# drive.net
KiCad netlist of a schematic drawn in Altium Designer
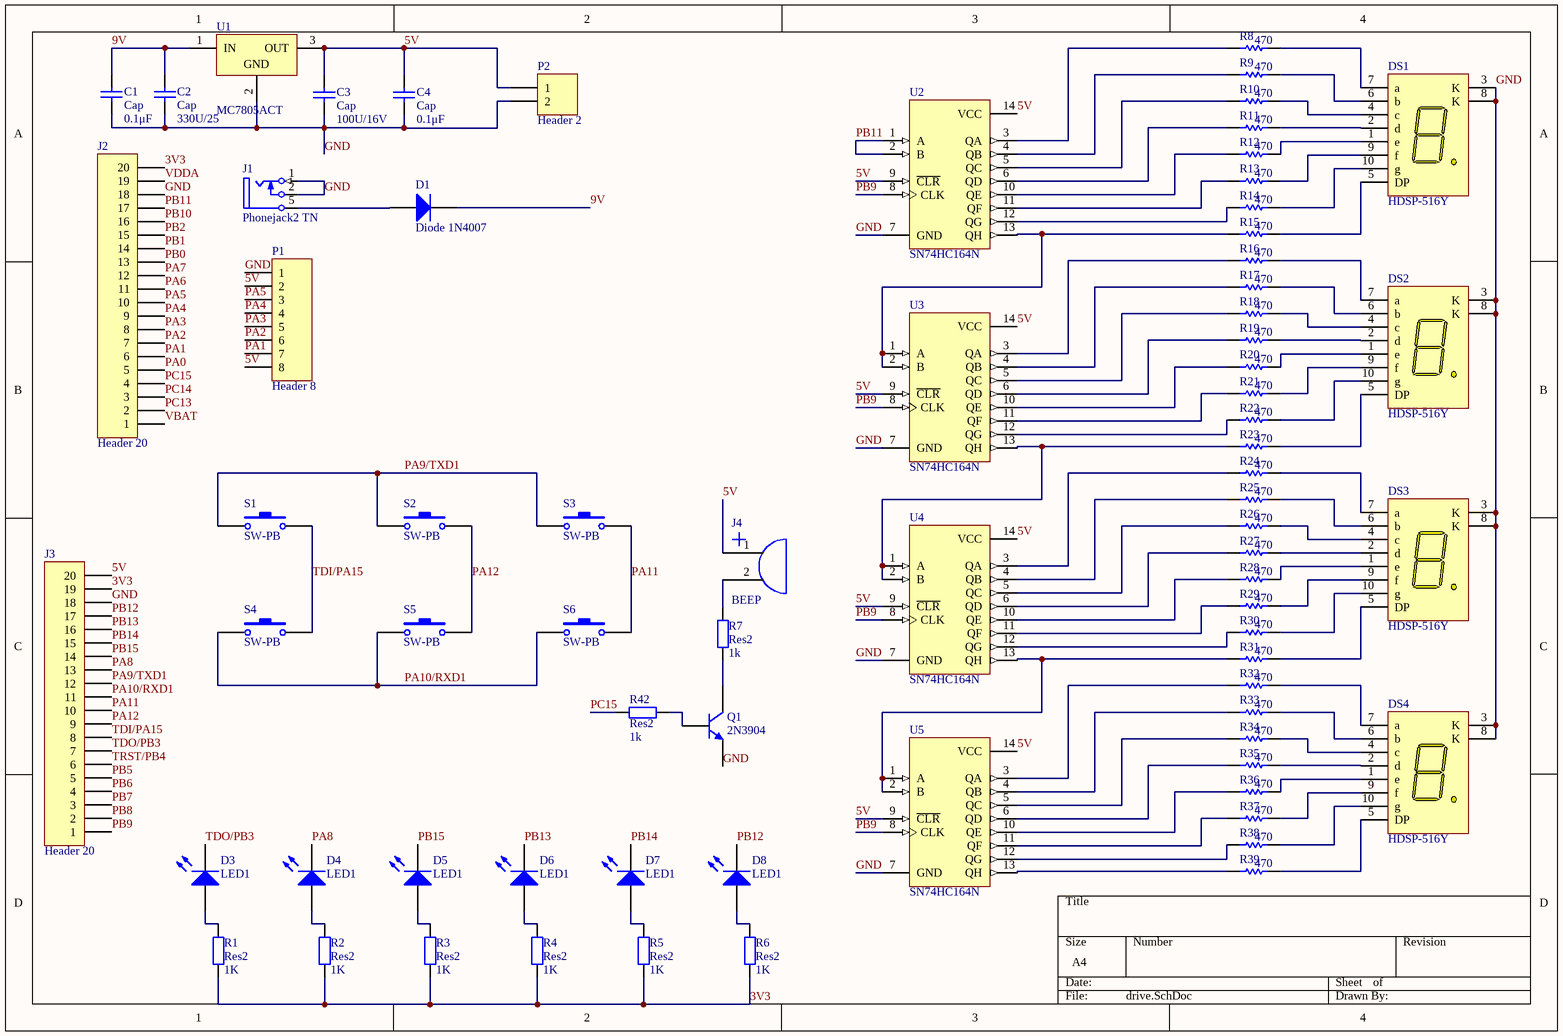
[diagram p0: drive.SchDoc]

(export (version "E")
  (design (tool "Eeschema 10.0.6"))
  (components
    (comp (ref "C1")
      (value "Cap")
      (footprint "RAD-0.3")
      (description "Capacitor")
      (fields (field (name "ALTIUM_VALUE") "0.1μF") (field (name "PUBLISHER") "Altium Limited"))
      (libsource (lib "Miscellaneous Devices") (part "Cap"))
    )
    (comp (ref "C2")
      (value "Cap")
      (footprint "RAD-0.3")
      (description "Capacitor")
      (fields (field (name "ALTIUM_VALUE") "330U/25") (field (name "PUBLISHER") "Altium Limited"))
      (libsource (lib "Miscellaneous Devices") (part "Cap"))
    )
    (comp (ref "C3")
      (value "Cap")
      (footprint "RAD-0.3")
      (description "Capacitor")
      (fields (field (name "ALTIUM_VALUE") "100U/16V") (field (name "PUBLISHER") "Altium Limited"))
      (libsource (lib "Miscellaneous Devices") (part "Cap"))
    )
    (comp (ref "C4")
      (value "Cap")
      (footprint "RAD-0.3")
      (description "Capacitor")
      (fields (field (name "ALTIUM_VALUE") "0.1μF") (field (name "PUBLISHER") "Altium Limited"))
      (libsource (lib "Miscellaneous Devices") (part "Cap"))
    )
    (comp (ref "D1")
      (value "Diode 1N4007")
      (footprint "DO-41")
      (description "1 Amp General Purpose Rectifier")
      (fields (field (name "PUBLISHER") "Altium Limited"))
      (libsource (lib "Miscellaneous Devices") (part "Diode 1N4007"))
    )
    (comp (ref "D3")
      (value "LED1")
      (footprint "LED-1")
      (description "Typical RED GaAs LED")
      (fields (field (name "PUBLISHER") "Altium Limited"))
      (libsource (lib "Miscellaneous Devices") (part "LED1"))
    )
    (comp (ref "D4")
      (value "LED1")
      (footprint "LED-1")
      (description "Typical RED GaAs LED")
      (fields (field (name "PUBLISHER") "Altium Limited"))
      (libsource (lib "Miscellaneous Devices") (part "LED1"))
    )
    (comp (ref "D5")
      (value "LED1")
      (footprint "LED-1")
      (description "Typical RED GaAs LED")
      (fields (field (name "PUBLISHER") "Altium Limited"))
      (libsource (lib "Miscellaneous Devices") (part "LED1"))
    )
    (comp (ref "D6")
      (value "LED1")
      (footprint "LED-1")
      (description "Typical RED GaAs LED")
      (fields (field (name "PUBLISHER") "Altium Limited"))
      (libsource (lib "Miscellaneous Devices") (part "LED1"))
    )
    (comp (ref "D7")
      (value "LED1")
      (footprint "LED-1")
      (description "Typical RED GaAs LED")
      (fields (field (name "PUBLISHER") "Altium Limited"))
      (libsource (lib "Miscellaneous Devices") (part "LED1"))
    )
    (comp (ref "D8")
      (value "LED1")
      (footprint "LED-1")
      (description "Typical RED GaAs LED")
      (fields (field (name "PUBLISHER") "Altium Limited"))
      (libsource (lib "Miscellaneous Devices") (part "LED1"))
    )
    (comp (ref "DS1")
      (value "HDSP-516Y")
      (footprint "Case-5")
      (description "13 mm Slim Font, Standard Current, Yellow 7-Segment Display: CC, RH DP")
      (fields (field (name "PUBLISHER") "Altium Limited"))
      (libsource (lib "Agilent LED Display 7-Segment, 1-Digit") (part "HDSP-516Y"))
    )
    (comp (ref "DS2")
      (value "HDSP-516Y")
      (footprint "Case-5")
      (description "13 mm Slim Font, Standard Current, Yellow 7-Segment Display: CC, RH DP")
      (fields (field (name "PUBLISHER") "Altium Limited"))
      (libsource (lib "Agilent LED Display 7-Segment, 1-Digit") (part "HDSP-516Y"))
    )
    (comp (ref "DS3")
      (value "HDSP-516Y")
      (footprint "Case-5")
      (description "13 mm Slim Font, Standard Current, Yellow 7-Segment Display: CC, RH DP")
      (fields (field (name "PUBLISHER") "Altium Limited"))
      (libsource (lib "Agilent LED Display 7-Segment, 1-Digit") (part "HDSP-516Y"))
    )
    (comp (ref "DS4")
      (value "HDSP-516Y")
      (footprint "Case-5")
      (description "13 mm Slim Font, Standard Current, Yellow 7-Segment Display: CC, RH DP")
      (fields (field (name "PUBLISHER") "Altium Limited"))
      (libsource (lib "Agilent LED Display 7-Segment, 1-Digit") (part "HDSP-516Y"))
    )
    (comp (ref "J1")
      (value "Phonejack2 TN")
      (footprint "DC-005")
      (description "Jack Socket, 1/4\" [6.5mm], Thru-Hole, Vertical, 2-Conductor with Tip closed")
      (fields (field (name "PUBLISHER") "Altium Limited"))
      (libsource (lib "Miscellaneous Connectors") (part "Phonejack2 TN"))
    )
    (comp (ref "J2")
      (value "Header 20")
      (footprint "HDR1X20")
      (description "Header, 20-Pin")
      (fields (field (name "PUBLISHER") "Altium Limited"))
      (libsource (lib "Miscellaneous Connectors") (part "Header 20"))
    )
    (comp (ref "J3")
      (value "Header 20")
      (footprint "HDR1X20")
      (description "Header, 20-Pin")
      (fields (field (name "PUBLISHER") "Altium Limited"))
      (libsource (lib "Miscellaneous Connectors") (part "Header 20"))
    )
    (comp (ref "J4")
      (value "BEEP")
      (footprint "Beep")
      (description "蜂鸣器")
      (libsource (lib "TSLone") (part "BEEP"))
    )
    (comp (ref "P1")
      (value "Header 8")
      (footprint "HDR1X8")
      (description "Header, 8-Pin")
      (fields (field (name "PUBLISHER") "Altium Limited"))
      (libsource (lib "Miscellaneous Connectors") (part "Header 8"))
    )
    (comp (ref "P2")
      (value "Header 2")
      (footprint "HDR1X2")
      (description "Header, 2-Pin")
      (fields (field (name "PUBLISHER") "Altium Limited"))
      (libsource (lib "Miscellaneous Connectors") (part "Header 2"))
    )
    (comp (ref "Q1")
      (value "2N3904")
      (footprint "TO-92A")
      (description "NPN General Purpose Amplifier")
      (fields (field (name "PUBLISHER") "Altium Limited"))
      (libsource (lib "Miscellaneous Devices") (part "2N3904"))
    )
    (comp (ref "R1")
      (value "Res2")
      (footprint "AXIAL-0.4")
      (description "Resistor")
      (fields (field (name "ALTIUM_VALUE") "1K") (field (name "PUBLISHER") "Altium Limited"))
      (libsource (lib "Miscellaneous Devices") (part "Res2"))
    )
    (comp (ref "R2")
      (value "Res2")
      (footprint "AXIAL-0.4")
      (description "Resistor")
      (fields (field (name "ALTIUM_VALUE") "1K") (field (name "PUBLISHER") "Altium Limited"))
      (libsource (lib "Miscellaneous Devices") (part "Res2"))
    )
    (comp (ref "R3")
      (value "Res2")
      (footprint "AXIAL-0.4")
      (description "Resistor")
      (fields (field (name "ALTIUM_VALUE") "1K") (field (name "PUBLISHER") "Altium Limited"))
      (libsource (lib "Miscellaneous Devices") (part "Res2"))
    )
    (comp (ref "R4")
      (value "Res2")
      (footprint "AXIAL-0.4")
      (description "Resistor")
      (fields (field (name "ALTIUM_VALUE") "1K") (field (name "PUBLISHER") "Altium Limited"))
      (libsource (lib "Miscellaneous Devices") (part "Res2"))
    )
    (comp (ref "R5")
      (value "Res2")
      (footprint "AXIAL-0.4")
      (description "Resistor")
      (fields (field (name "ALTIUM_VALUE") "1K") (field (name "PUBLISHER") "Altium Limited"))
      (libsource (lib "Miscellaneous Devices") (part "Res2"))
    )
    (comp (ref "R6")
      (value "Res2")
      (footprint "AXIAL-0.4")
      (description "Resistor")
      (fields (field (name "ALTIUM_VALUE") "1K") (field (name "PUBLISHER") "Altium Limited"))
      (libsource (lib "Miscellaneous Devices") (part "Res2"))
    )
    (comp (ref "R7")
      (value "Res2")
      (footprint "AXIAL-0.4")
      (description "Resistor")
      (fields (field (name "ALTIUM_VALUE") "1k") (field (name "PUBLISHER") "Altium Limited"))
      (libsource (lib "Miscellaneous Devices") (part "Res2"))
    )
    (comp (ref "R8")
      (value "470")
      (footprint "AXIAL-0.3")
      (description "Resistor")
      (fields (field (name "Comment") "Res1") (field (name "PUBLISHER") "Altium Limited"))
      (libsource (lib "Miscellaneous Devices") (part "Res1"))
    )
    (comp (ref "R9")
      (value "470")
      (footprint "AXIAL-0.3")
      (description "Resistor")
      (fields (field (name "Comment") "Res1") (field (name "PUBLISHER") "Altium Limited"))
      (libsource (lib "Miscellaneous Devices") (part "Res1"))
    )
    (comp (ref "R10")
      (value "470")
      (footprint "AXIAL-0.3")
      (description "Resistor")
      (fields (field (name "Comment") "Res1") (field (name "PUBLISHER") "Altium Limited"))
      (libsource (lib "Miscellaneous Devices") (part "Res1"))
    )
    (comp (ref "R11")
      (value "470")
      (footprint "AXIAL-0.3")
      (description "Resistor")
      (fields (field (name "Comment") "Res1") (field (name "PUBLISHER") "Altium Limited"))
      (libsource (lib "Miscellaneous Devices") (part "Res1"))
    )
    (comp (ref "R12")
      (value "470")
      (footprint "AXIAL-0.3")
      (description "Resistor")
      (fields (field (name "Comment") "Res1") (field (name "PUBLISHER") "Altium Limited"))
      (libsource (lib "Miscellaneous Devices") (part "Res1"))
    )
    (comp (ref "R13")
      (value "470")
      (footprint "AXIAL-0.3")
      (description "Resistor")
      (fields (field (name "Comment") "Res1") (field (name "PUBLISHER") "Altium Limited"))
      (libsource (lib "Miscellaneous Devices") (part "Res1"))
    )
    (comp (ref "R14")
      (value "470")
      (footprint "AXIAL-0.3")
      (description "Resistor")
      (fields (field (name "Comment") "Res1") (field (name "PUBLISHER") "Altium Limited"))
      (libsource (lib "Miscellaneous Devices") (part "Res1"))
    )
    (comp (ref "R15")
      (value "470")
      (footprint "AXIAL-0.3")
      (description "Resistor")
      (fields (field (name "Comment") "Res1") (field (name "PUBLISHER") "Altium Limited"))
      (libsource (lib "Miscellaneous Devices") (part "Res1"))
    )
    (comp (ref "R16")
      (value "470")
      (footprint "AXIAL-0.3")
      (description "Resistor")
      (fields (field (name "Comment") "Res1") (field (name "PUBLISHER") "Altium Limited"))
      (libsource (lib "Miscellaneous Devices") (part "Res1"))
    )
    (comp (ref "R17")
      (value "470")
      (footprint "AXIAL-0.3")
      (description "Resistor")
      (fields (field (name "Comment") "Res1") (field (name "PUBLISHER") "Altium Limited"))
      (libsource (lib "Miscellaneous Devices") (part "Res1"))
    )
    (comp (ref "R18")
      (value "470")
      (footprint "AXIAL-0.3")
      (description "Resistor")
      (fields (field (name "Comment") "Res1") (field (name "PUBLISHER") "Altium Limited"))
      (libsource (lib "Miscellaneous Devices") (part "Res1"))
    )
    (comp (ref "R19")
      (value "470")
      (footprint "AXIAL-0.3")
      (description "Resistor")
      (fields (field (name "Comment") "Res1") (field (name "PUBLISHER") "Altium Limited"))
      (libsource (lib "Miscellaneous Devices") (part "Res1"))
    )
    (comp (ref "R20")
      (value "470")
      (footprint "AXIAL-0.3")
      (description "Resistor")
      (fields (field (name "Comment") "Res1") (field (name "PUBLISHER") "Altium Limited"))
      (libsource (lib "Miscellaneous Devices") (part "Res1"))
    )
    (comp (ref "R21")
      (value "470")
      (footprint "AXIAL-0.3")
      (description "Resistor")
      (fields (field (name "Comment") "Res1") (field (name "PUBLISHER") "Altium Limited"))
      (libsource (lib "Miscellaneous Devices") (part "Res1"))
    )
    (comp (ref "R22")
      (value "470")
      (footprint "AXIAL-0.3")
      (description "Resistor")
      (fields (field (name "Comment") "Res1") (field (name "PUBLISHER") "Altium Limited"))
      (libsource (lib "Miscellaneous Devices") (part "Res1"))
    )
    (comp (ref "R23")
      (value "470")
      (footprint "AXIAL-0.3")
      (description "Resistor")
      (fields (field (name "Comment") "Res1") (field (name "PUBLISHER") "Altium Limited"))
      (libsource (lib "Miscellaneous Devices") (part "Res1"))
    )
    (comp (ref "R24")
      (value "470")
      (footprint "AXIAL-0.3")
      (description "Resistor")
      (fields (field (name "Comment") "Res1") (field (name "PUBLISHER") "Altium Limited"))
      (libsource (lib "Miscellaneous Devices") (part "Res1"))
    )
    (comp (ref "R25")
      (value "470")
      (footprint "AXIAL-0.3")
      (description "Resistor")
      (fields (field (name "Comment") "Res1") (field (name "PUBLISHER") "Altium Limited"))
      (libsource (lib "Miscellaneous Devices") (part "Res1"))
    )
    (comp (ref "R26")
      (value "470")
      (footprint "AXIAL-0.3")
      (description "Resistor")
      (fields (field (name "Comment") "Res1") (field (name "PUBLISHER") "Altium Limited"))
      (libsource (lib "Miscellaneous Devices") (part "Res1"))
    )
    (comp (ref "R27")
      (value "470")
      (footprint "AXIAL-0.3")
      (description "Resistor")
      (fields (field (name "Comment") "Res1") (field (name "PUBLISHER") "Altium Limited"))
      (libsource (lib "Miscellaneous Devices") (part "Res1"))
    )
    (comp (ref "R28")
      (value "470")
      (footprint "AXIAL-0.3")
      (description "Resistor")
      (fields (field (name "Comment") "Res1") (field (name "PUBLISHER") "Altium Limited"))
      (libsource (lib "Miscellaneous Devices") (part "Res1"))
    )
    (comp (ref "R29")
      (value "470")
      (footprint "AXIAL-0.3")
      (description "Resistor")
      (fields (field (name "Comment") "Res1") (field (name "PUBLISHER") "Altium Limited"))
      (libsource (lib "Miscellaneous Devices") (part "Res1"))
    )
    (comp (ref "R30")
      (value "470")
      (footprint "AXIAL-0.3")
      (description "Resistor")
      (fields (field (name "Comment") "Res1") (field (name "PUBLISHER") "Altium Limited"))
      (libsource (lib "Miscellaneous Devices") (part "Res1"))
    )
    (comp (ref "R31")
      (value "470")
      (footprint "AXIAL-0.3")
      (description "Resistor")
      (fields (field (name "Comment") "Res1") (field (name "PUBLISHER") "Altium Limited"))
      (libsource (lib "Miscellaneous Devices") (part "Res1"))
    )
    (comp (ref "R32")
      (value "470")
      (footprint "AXIAL-0.3")
      (description "Resistor")
      (fields (field (name "Comment") "Res1") (field (name "PUBLISHER") "Altium Limited"))
      (libsource (lib "Miscellaneous Devices") (part "Res1"))
    )
    (comp (ref "R33")
      (value "470")
      (footprint "AXIAL-0.3")
      (description "Resistor")
      (fields (field (name "Comment") "Res1") (field (name "PUBLISHER") "Altium Limited"))
      (libsource (lib "Miscellaneous Devices") (part "Res1"))
    )
    (comp (ref "R34")
      (value "470")
      (footprint "AXIAL-0.3")
      (description "Resistor")
      (fields (field (name "Comment") "Res1") (field (name "PUBLISHER") "Altium Limited"))
      (libsource (lib "Miscellaneous Devices") (part "Res1"))
    )
    (comp (ref "R35")
      (value "470")
      (footprint "AXIAL-0.3")
      (description "Resistor")
      (fields (field (name "Comment") "Res1") (field (name "PUBLISHER") "Altium Limited"))
      (libsource (lib "Miscellaneous Devices") (part "Res1"))
    )
    (comp (ref "R36")
      (value "470")
      (footprint "AXIAL-0.3")
      (description "Resistor")
      (fields (field (name "Comment") "Res1") (field (name "PUBLISHER") "Altium Limited"))
      (libsource (lib "Miscellaneous Devices") (part "Res1"))
    )
    (comp (ref "R37")
      (value "470")
      (footprint "AXIAL-0.3")
      (description "Resistor")
      (fields (field (name "Comment") "Res1") (field (name "PUBLISHER") "Altium Limited"))
      (libsource (lib "Miscellaneous Devices") (part "Res1"))
    )
    (comp (ref "R38")
      (value "470")
      (footprint "AXIAL-0.3")
      (description "Resistor")
      (fields (field (name "Comment") "Res1") (field (name "PUBLISHER") "Altium Limited"))
      (libsource (lib "Miscellaneous Devices") (part "Res1"))
    )
    (comp (ref "R39")
      (value "470")
      (footprint "AXIAL-0.3")
      (description "Resistor")
      (fields (field (name "Comment") "Res1") (field (name "PUBLISHER") "Altium Limited"))
      (libsource (lib "Miscellaneous Devices") (part "Res1"))
    )
    (comp (ref "R42")
      (value "Res2")
      (footprint "AXIAL-0.4")
      (description "Resistor")
      (fields (field (name "ALTIUM_VALUE") "1k") (field (name "PUBLISHER") "Altium Limited"))
      (libsource (lib "") (part "Res2_1"))
    )
    (comp (ref "S1")
      (value "SW-PB")
      (footprint "SW9")
      (description "微动开关")
      (fields (field (name "PUBLISHER") "Altium Limited"))
      (libsource (lib "TSLone") (part "SW-PB"))
    )
    (comp (ref "S2")
      (value "SW-PB")
      (footprint "SW9")
      (description "微动开关")
      (fields (field (name "PUBLISHER") "Altium Limited"))
      (libsource (lib "TSLone") (part "SW-PB"))
    )
    (comp (ref "S3")
      (value "SW-PB")
      (footprint "SW9")
      (description "微动开关")
      (fields (field (name "PUBLISHER") "Altium Limited"))
      (libsource (lib "TSLone") (part "SW-PB"))
    )
    (comp (ref "S4")
      (value "SW-PB")
      (footprint "SW9")
      (description "微动开关")
      (fields (field (name "PUBLISHER") "Altium Limited"))
      (libsource (lib "TSLone") (part "SW-PB"))
    )
    (comp (ref "S5")
      (value "SW-PB")
      (footprint "SW9")
      (description "微动开关")
      (fields (field (name "PUBLISHER") "Altium Limited"))
      (libsource (lib "TSLone") (part "SW-PB"))
    )
    (comp (ref "S6")
      (value "SW-PB")
      (footprint "SW9")
      (description "微动开关")
      (fields (field (name "PUBLISHER") "Altium Limited"))
      (libsource (lib "TSLone") (part "SW-PB"))
    )
    (comp (ref "U1")
      (value "MC7805ACT")
      (footprint "221A-06")
      (description "Three-Terminal Positive Voltage Regulator")
      (fields (field (name "PUBLISHER") "Altium Limited"))
      (libsource (lib "ON Semi Power Mgt Voltage Regulator") (part "MC7805ACT"))
    )
    (comp (ref "U2")
      (value "SN74HC164N")
      (footprint "N014")
      (description "8-Bit Parallel-Out Serial Shift Register")
      (fields (field (name "PUBLISHER") "Altium Limited"))
      (libsource (lib "TI Logic Register") (part "SN74HC164N"))
    )
    (comp (ref "U3")
      (value "SN74HC164N")
      (footprint "N014")
      (description "8-Bit Parallel-Out Serial Shift Register")
      (fields (field (name "PUBLISHER") "Altium Limited"))
      (libsource (lib "TI Logic Register") (part "SN74HC164N"))
    )
    (comp (ref "U4")
      (value "SN74HC164N")
      (footprint "N014")
      (description "8-Bit Parallel-Out Serial Shift Register")
      (fields (field (name "PUBLISHER") "Altium Limited"))
      (libsource (lib "TI Logic Register") (part "SN74HC164N"))
    )
    (comp (ref "U5")
      (value "SN74HC164N")
      (footprint "N014")
      (description "8-Bit Parallel-Out Serial Shift Register")
      (fields (field (name "PUBLISHER") "Altium Limited"))
      (libsource (lib "TI Logic Register") (part "SN74HC164N"))
    )
  )
  (nets
    (net (code "1") (name "/3V3") (class "Default")
      (node (ref "J2") (pin "20") (pinfunction "20_20") (pintype "passive"))
      (node (ref "J3") (pin "19") (pinfunction "19_19") (pintype "passive"))
      (node (ref "R1") (pin "1") (pinfunction "1_1") (pintype "passive"))
      (node (ref "R2") (pin "1") (pinfunction "1_1") (pintype "passive"))
      (node (ref "R3") (pin "1") (pinfunction "1_1") (pintype "passive"))
      (node (ref "R4") (pin "1") (pinfunction "1_1") (pintype "passive"))
      (node (ref "R5") (pin "1") (pinfunction "1_1") (pintype "passive"))
      (node (ref "R6") (pin "1") (pinfunction "1_1") (pintype "passive"))
    )
    (net (code "2") (name "/5V") (class "Default")
      (node (ref "C3") (pin "1") (pinfunction "1_1") (pintype "passive"))
      (node (ref "C4") (pin "1") (pinfunction "1_1") (pintype "passive"))
      (node (ref "J3") (pin "20") (pinfunction "20_20") (pintype "passive"))
      (node (ref "J4") (pin "1") (pinfunction "0_1") (pintype "passive"))
      (node (ref "P1") (pin "2") (pinfunction "2_2") (pintype "passive"))
      (node (ref "P1") (pin "8") (pinfunction "8_8") (pintype "passive"))
      (node (ref "P2") (pin "1") (pinfunction "1_1") (pintype "passive"))
      (node (ref "U1") (pin "3") (pinfunction "OUT_3") (pintype "power_in"))
      (node (ref "U2") (pin "14") (pinfunction "VCC_14") (pintype "power_in"))
      (node (ref "U2") (pin "9") (pinfunction "~{CLR}_9") (pintype "input"))
      (node (ref "U3") (pin "14") (pinfunction "VCC_14") (pintype "power_in"))
      (node (ref "U3") (pin "9") (pinfunction "~{CLR}_9") (pintype "input"))
      (node (ref "U4") (pin "14") (pinfunction "VCC_14") (pintype "power_in"))
      (node (ref "U4") (pin "9") (pinfunction "~{CLR}_9") (pintype "input"))
      (node (ref "U5") (pin "14") (pinfunction "VCC_14") (pintype "power_in"))
      (node (ref "U5") (pin "9") (pinfunction "~{CLR}_9") (pintype "input"))
    )
    (net (code "3") (name "/9V") (class "Default")
      (node (ref "C1") (pin "1") (pinfunction "1_1") (pintype "passive"))
      (node (ref "C2") (pin "1") (pinfunction "1_1") (pintype "passive"))
      (node (ref "D1") (pin "2") (pinfunction "K_2") (pintype "passive"))
      (node (ref "U1") (pin "1") (pinfunction "IN_1") (pintype "power_in"))
    )
    (net (code "4") (name "/GND") (class "Default")
      (node (ref "C1") (pin "2") (pinfunction "2_2") (pintype "passive"))
      (node (ref "C2") (pin "2") (pinfunction "2_2") (pintype "passive"))
      (node (ref "C3") (pin "2") (pinfunction "2_2") (pintype "passive"))
      (node (ref "C4") (pin "2") (pinfunction "2_2") (pintype "passive"))
      (node (ref "DS1") (pin "3") (pinfunction "K_3") (pintype "passive"))
      (node (ref "DS1") (pin "8") (pinfunction "K_8") (pintype "passive"))
      (node (ref "DS2") (pin "3") (pinfunction "K_3") (pintype "passive"))
      (node (ref "DS2") (pin "8") (pinfunction "K_8") (pintype "passive"))
      (node (ref "DS3") (pin "3") (pinfunction "K_3") (pintype "passive"))
      (node (ref "DS3") (pin "8") (pinfunction "K_8") (pintype "passive"))
      (node (ref "DS4") (pin "3") (pinfunction "K_3") (pintype "passive"))
      (node (ref "DS4") (pin "8") (pinfunction "K_8") (pintype "passive"))
      (node (ref "J1") (pin "1") (pinfunction "T_1") (pintype "input"))
      (node (ref "J1") (pin "2") (pinfunction "TN_2") (pintype "passive"))
      (node (ref "J2") (pin "18") (pinfunction "18_18") (pintype "passive"))
      (node (ref "J3") (pin "18") (pinfunction "18_18") (pintype "passive"))
      (node (ref "P1") (pin "1") (pinfunction "1_1") (pintype "passive"))
      (node (ref "P2") (pin "2") (pinfunction "2_2") (pintype "passive"))
      (node (ref "Q1") (pin "1") (pinfunction "E_1") (pintype "passive"))
      (node (ref "U1") (pin "2") (pinfunction "GND_2") (pintype "power_in"))
      (node (ref "U2") (pin "7") (pinfunction "GND_7") (pintype "power_in"))
      (node (ref "U3") (pin "7") (pinfunction "GND_7") (pintype "power_in"))
      (node (ref "U4") (pin "7") (pinfunction "GND_7") (pintype "power_in"))
      (node (ref "U5") (pin "7") (pinfunction "GND_7") (pintype "power_in"))
    )
    (net (code "5") (name "/PA0") (class "Default")
      (node (ref "J2") (pin "5") (pinfunction "5_5") (pintype "passive"))
    )
    (net (code "6") (name "/PA1") (class "Default")
      (node (ref "J2") (pin "6") (pinfunction "6_6") (pintype "passive"))
      (node (ref "P1") (pin "7") (pinfunction "7_7") (pintype "passive"))
    )
    (net (code "7") (name "/PA2") (class "Default")
      (node (ref "J2") (pin "7") (pinfunction "7_7") (pintype "passive"))
      (node (ref "P1") (pin "6") (pinfunction "6_6") (pintype "passive"))
    )
    (net (code "8") (name "/PA3") (class "Default")
      (node (ref "J2") (pin "8") (pinfunction "8_8") (pintype "passive"))
      (node (ref "P1") (pin "5") (pinfunction "5_5") (pintype "passive"))
    )
    (net (code "9") (name "/PA4") (class "Default")
      (node (ref "J2") (pin "9") (pinfunction "9_9") (pintype "passive"))
      (node (ref "P1") (pin "4") (pinfunction "4_4") (pintype "passive"))
    )
    (net (code "10") (name "/PA5") (class "Default")
      (node (ref "J2") (pin "10") (pinfunction "10_10") (pintype "passive"))
      (node (ref "P1") (pin "3") (pinfunction "3_3") (pintype "passive"))
    )
    (net (code "11") (name "/PA6") (class "Default")
      (node (ref "J2") (pin "11") (pinfunction "11_11") (pintype "passive"))
    )
    (net (code "12") (name "/PA7") (class "Default")
      (node (ref "J2") (pin "12") (pinfunction "12_12") (pintype "passive"))
    )
    (net (code "13") (name "/PA8") (class "Default")
      (node (ref "D4") (pin "2") (pinfunction "K_2") (pintype "passive"))
      (node (ref "J3") (pin "13") (pinfunction "13_13") (pintype "passive"))
    )
    (net (code "14") (name "/PA9{slash}TXD1") (class "Default")
      (node (ref "J3") (pin "12") (pinfunction "12_12") (pintype "passive"))
      (node (ref "S1") (pin "1") (pinfunction "1_1") (pintype "passive"))
      (node (ref "S2") (pin "1") (pinfunction "1_1") (pintype "passive"))
      (node (ref "S3") (pin "1") (pinfunction "1_1") (pintype "passive"))
    )
    (net (code "15") (name "/PA10{slash}RXD1") (class "Default")
      (node (ref "J3") (pin "11") (pinfunction "11_11") (pintype "passive"))
      (node (ref "S4") (pin "1") (pinfunction "1_1") (pintype "passive"))
      (node (ref "S5") (pin "1") (pinfunction "1_1") (pintype "passive"))
      (node (ref "S6") (pin "1") (pinfunction "1_1") (pintype "passive"))
    )
    (net (code "16") (name "/PA11") (class "Default")
      (node (ref "J3") (pin "10") (pinfunction "10_10") (pintype "passive"))
      (node (ref "S3") (pin "2") (pinfunction "2_2") (pintype "passive"))
      (node (ref "S6") (pin "2") (pinfunction "2_2") (pintype "passive"))
    )
    (net (code "17") (name "/PA12") (class "Default")
      (node (ref "J3") (pin "9") (pinfunction "9_9") (pintype "passive"))
      (node (ref "S2") (pin "2") (pinfunction "2_2") (pintype "passive"))
      (node (ref "S5") (pin "2") (pinfunction "2_2") (pintype "passive"))
    )
    (net (code "18") (name "/PB0") (class "Default")
      (node (ref "J2") (pin "13") (pinfunction "13_13") (pintype "passive"))
    )
    (net (code "19") (name "/PB1") (class "Default")
      (node (ref "J2") (pin "14") (pinfunction "14_14") (pintype "passive"))
    )
    (net (code "20") (name "/PB2") (class "Default")
      (node (ref "J2") (pin "15") (pinfunction "15_15") (pintype "passive"))
    )
    (net (code "21") (name "/PB5") (class "Default")
      (node (ref "J3") (pin "5") (pinfunction "5_5") (pintype "passive"))
    )
    (net (code "22") (name "/PB6") (class "Default")
      (node (ref "J3") (pin "4") (pinfunction "4_4") (pintype "passive"))
    )
    (net (code "23") (name "/PB7") (class "Default")
      (node (ref "J3") (pin "3") (pinfunction "3_3") (pintype "passive"))
    )
    (net (code "24") (name "/PB8") (class "Default")
      (node (ref "J3") (pin "2") (pinfunction "2_2") (pintype "passive"))
    )
    (net (code "25") (name "/PB9") (class "Default")
      (node (ref "J3") (pin "1") (pinfunction "1_1") (pintype "passive"))
      (node (ref "U2") (pin "8") (pinfunction "CLK_8") (pintype "input"))
      (node (ref "U3") (pin "8") (pinfunction "CLK_8") (pintype "input"))
      (node (ref "U4") (pin "8") (pinfunction "CLK_8") (pintype "input"))
      (node (ref "U5") (pin "8") (pinfunction "CLK_8") (pintype "input"))
    )
    (net (code "26") (name "/PB10") (class "Default")
      (node (ref "J2") (pin "16") (pinfunction "16_16") (pintype "passive"))
    )
    (net (code "27") (name "/PB11") (class "Default")
      (node (ref "J2") (pin "17") (pinfunction "17_17") (pintype "passive"))
      (node (ref "U2") (pin "1") (pinfunction "A_1") (pintype "input"))
      (node (ref "U2") (pin "2") (pinfunction "B_2") (pintype "input"))
    )
    (net (code "28") (name "/PB12") (class "Default")
      (node (ref "D8") (pin "2") (pinfunction "K_2") (pintype "passive"))
      (node (ref "J3") (pin "17") (pinfunction "17_17") (pintype "passive"))
    )
    (net (code "29") (name "/PB13") (class "Default")
      (node (ref "D6") (pin "2") (pinfunction "K_2") (pintype "passive"))
      (node (ref "J3") (pin "16") (pinfunction "16_16") (pintype "passive"))
    )
    (net (code "30") (name "/PB14") (class "Default")
      (node (ref "D7") (pin "2") (pinfunction "K_2") (pintype "passive"))
      (node (ref "J3") (pin "15") (pinfunction "15_15") (pintype "passive"))
    )
    (net (code "31") (name "/PB15") (class "Default")
      (node (ref "D5") (pin "2") (pinfunction "K_2") (pintype "passive"))
      (node (ref "J3") (pin "14") (pinfunction "14_14") (pintype "passive"))
    )
    (net (code "32") (name "/PC13") (class "Default")
      (node (ref "J2") (pin "2") (pinfunction "2_2") (pintype "passive"))
    )
    (net (code "33") (name "/PC14") (class "Default")
      (node (ref "J2") (pin "3") (pinfunction "3_3") (pintype "passive"))
    )
    (net (code "34") (name "/PC15") (class "Default")
      (node (ref "J2") (pin "4") (pinfunction "4_4") (pintype "passive"))
      (node (ref "R42") (pin "2") (pinfunction "2_2") (pintype "passive"))
    )
    (net (code "35") (name "/TDI{slash}PA15") (class "Default")
      (node (ref "J3") (pin "8") (pinfunction "8_8") (pintype "passive"))
      (node (ref "S1") (pin "2") (pinfunction "2_2") (pintype "passive"))
      (node (ref "S4") (pin "2") (pinfunction "2_2") (pintype "passive"))
    )
    (net (code "36") (name "/TDO{slash}PB3") (class "Default")
      (node (ref "D3") (pin "2") (pinfunction "K_2") (pintype "passive"))
      (node (ref "J3") (pin "7") (pinfunction "7_7") (pintype "passive"))
    )
    (net (code "37") (name "/TRST{slash}PB4") (class "Default")
      (node (ref "J3") (pin "6") (pinfunction "6_6") (pintype "passive"))
    )
    (net (code "38") (name "/VBAT") (class "Default")
      (node (ref "J2") (pin "1") (pinfunction "1_1") (pintype "passive"))
    )
    (net (code "39") (name "/VDDA") (class "Default")
      (node (ref "J2") (pin "19") (pinfunction "19_19") (pintype "passive"))
    )
    (net (code "40") (name "Net-(D1-A)") (class "Default")
      (node (ref "D1") (pin "1") (pinfunction "A_1") (pintype "passive"))
      (node (ref "J1") (pin "5") (pinfunction "S_5") (pintype "power_in"))
    )
    (net (code "41") (name "Net-(D3-A)") (class "Default")
      (node (ref "D3") (pin "1") (pinfunction "A_1") (pintype "passive"))
      (node (ref "R1") (pin "2") (pinfunction "2_2") (pintype "passive"))
    )
    (net (code "42") (name "Net-(D4-A)") (class "Default")
      (node (ref "D4") (pin "1") (pinfunction "A_1") (pintype "passive"))
      (node (ref "R2") (pin "2") (pinfunction "2_2") (pintype "passive"))
    )
    (net (code "43") (name "Net-(D5-A)") (class "Default")
      (node (ref "D5") (pin "1") (pinfunction "A_1") (pintype "passive"))
      (node (ref "R3") (pin "2") (pinfunction "2_2") (pintype "passive"))
    )
    (net (code "44") (name "Net-(D6-A)") (class "Default")
      (node (ref "D6") (pin "1") (pinfunction "A_1") (pintype "passive"))
      (node (ref "R4") (pin "2") (pinfunction "2_2") (pintype "passive"))
    )
    (net (code "45") (name "Net-(D7-A)") (class "Default")
      (node (ref "D7") (pin "1") (pinfunction "A_1") (pintype "passive"))
      (node (ref "R5") (pin "2") (pinfunction "2_2") (pintype "passive"))
    )
    (net (code "46") (name "Net-(D8-A)") (class "Default")
      (node (ref "D8") (pin "1") (pinfunction "A_1") (pintype "passive"))
      (node (ref "R6") (pin "2") (pinfunction "2_2") (pintype "passive"))
    )
    (net (code "47") (name "Net-(DS1-DP)") (class "Default")
      (node (ref "DS1") (pin "5") (pinfunction "DP_5") (pintype "passive"))
      (node (ref "R15") (pin "2") (pinfunction "2_2") (pintype "passive"))
    )
    (net (code "48") (name "Net-(DS1-a)") (class "Default")
      (node (ref "DS1") (pin "7") (pinfunction "a_7") (pintype "passive"))
      (node (ref "R8") (pin "2") (pinfunction "2_2") (pintype "passive"))
    )
    (net (code "49") (name "Net-(DS1-b)") (class "Default")
      (node (ref "DS1") (pin "6") (pinfunction "b_6") (pintype "passive"))
      (node (ref "R9") (pin "2") (pinfunction "2_2") (pintype "passive"))
    )
    (net (code "50") (name "Net-(DS1-c)") (class "Default")
      (node (ref "DS1") (pin "4") (pinfunction "c_4") (pintype "passive"))
      (node (ref "R10") (pin "2") (pinfunction "2_2") (pintype "passive"))
    )
    (net (code "51") (name "Net-(DS1-d)") (class "Default")
      (node (ref "DS1") (pin "2") (pinfunction "d_2") (pintype "passive"))
      (node (ref "R11") (pin "2") (pinfunction "2_2") (pintype "passive"))
    )
    (net (code "52") (name "Net-(DS1-e)") (class "Default")
      (node (ref "DS1") (pin "1") (pinfunction "e_1") (pintype "passive"))
      (node (ref "R12") (pin "2") (pinfunction "2_2") (pintype "passive"))
    )
    (net (code "53") (name "Net-(DS1-f)") (class "Default")
      (node (ref "DS1") (pin "9") (pinfunction "f_9") (pintype "passive"))
      (node (ref "R13") (pin "2") (pinfunction "2_2") (pintype "passive"))
    )
    (net (code "54") (name "Net-(DS1-g)") (class "Default")
      (node (ref "DS1") (pin "10") (pinfunction "g_10") (pintype "passive"))
      (node (ref "R14") (pin "2") (pinfunction "2_2") (pintype "passive"))
    )
    (net (code "55") (name "Net-(DS2-DP)") (class "Default")
      (node (ref "DS2") (pin "5") (pinfunction "DP_5") (pintype "passive"))
      (node (ref "R23") (pin "2") (pinfunction "2_2") (pintype "passive"))
    )
    (net (code "56") (name "Net-(DS2-a)") (class "Default")
      (node (ref "DS2") (pin "7") (pinfunction "a_7") (pintype "passive"))
      (node (ref "R16") (pin "2") (pinfunction "2_2") (pintype "passive"))
    )
    (net (code "57") (name "Net-(DS2-b)") (class "Default")
      (node (ref "DS2") (pin "6") (pinfunction "b_6") (pintype "passive"))
      (node (ref "R17") (pin "2") (pinfunction "2_2") (pintype "passive"))
    )
    (net (code "58") (name "Net-(DS2-c)") (class "Default")
      (node (ref "DS2") (pin "4") (pinfunction "c_4") (pintype "passive"))
      (node (ref "R18") (pin "2") (pinfunction "2_2") (pintype "passive"))
    )
    (net (code "59") (name "Net-(DS2-d)") (class "Default")
      (node (ref "DS2") (pin "2") (pinfunction "d_2") (pintype "passive"))
      (node (ref "R19") (pin "2") (pinfunction "2_2") (pintype "passive"))
    )
    (net (code "60") (name "Net-(DS2-e)") (class "Default")
      (node (ref "DS2") (pin "1") (pinfunction "e_1") (pintype "passive"))
      (node (ref "R20") (pin "2") (pinfunction "2_2") (pintype "passive"))
    )
    (net (code "61") (name "Net-(DS2-f)") (class "Default")
      (node (ref "DS2") (pin "9") (pinfunction "f_9") (pintype "passive"))
      (node (ref "R21") (pin "2") (pinfunction "2_2") (pintype "passive"))
    )
    (net (code "62") (name "Net-(DS2-g)") (class "Default")
      (node (ref "DS2") (pin "10") (pinfunction "g_10") (pintype "passive"))
      (node (ref "R22") (pin "2") (pinfunction "2_2") (pintype "passive"))
    )
    (net (code "63") (name "Net-(DS3-DP)") (class "Default")
      (node (ref "DS3") (pin "5") (pinfunction "DP_5") (pintype "passive"))
      (node (ref "R31") (pin "2") (pinfunction "2_2") (pintype "passive"))
    )
    (net (code "64") (name "Net-(DS3-a)") (class "Default")
      (node (ref "DS3") (pin "7") (pinfunction "a_7") (pintype "passive"))
      (node (ref "R24") (pin "2") (pinfunction "2_2") (pintype "passive"))
    )
    (net (code "65") (name "Net-(DS3-b)") (class "Default")
      (node (ref "DS3") (pin "6") (pinfunction "b_6") (pintype "passive"))
      (node (ref "R25") (pin "2") (pinfunction "2_2") (pintype "passive"))
    )
    (net (code "66") (name "Net-(DS3-c)") (class "Default")
      (node (ref "DS3") (pin "4") (pinfunction "c_4") (pintype "passive"))
      (node (ref "R26") (pin "2") (pinfunction "2_2") (pintype "passive"))
    )
    (net (code "67") (name "Net-(DS3-d)") (class "Default")
      (node (ref "DS3") (pin "2") (pinfunction "d_2") (pintype "passive"))
      (node (ref "R27") (pin "2") (pinfunction "2_2") (pintype "passive"))
    )
    (net (code "68") (name "Net-(DS3-e)") (class "Default")
      (node (ref "DS3") (pin "1") (pinfunction "e_1") (pintype "passive"))
      (node (ref "R28") (pin "2") (pinfunction "2_2") (pintype "passive"))
    )
    (net (code "69") (name "Net-(DS3-f)") (class "Default")
      (node (ref "DS3") (pin "9") (pinfunction "f_9") (pintype "passive"))
      (node (ref "R29") (pin "2") (pinfunction "2_2") (pintype "passive"))
    )
    (net (code "70") (name "Net-(DS3-g)") (class "Default")
      (node (ref "DS3") (pin "10") (pinfunction "g_10") (pintype "passive"))
      (node (ref "R30") (pin "2") (pinfunction "2_2") (pintype "passive"))
    )
    (net (code "71") (name "Net-(DS4-DP)") (class "Default")
      (node (ref "DS4") (pin "5") (pinfunction "DP_5") (pintype "passive"))
      (node (ref "R39") (pin "2") (pinfunction "2_2") (pintype "passive"))
    )
    (net (code "72") (name "Net-(DS4-a)") (class "Default")
      (node (ref "DS4") (pin "7") (pinfunction "a_7") (pintype "passive"))
      (node (ref "R32") (pin "2") (pinfunction "2_2") (pintype "passive"))
    )
    (net (code "73") (name "Net-(DS4-b)") (class "Default")
      (node (ref "DS4") (pin "6") (pinfunction "b_6") (pintype "passive"))
      (node (ref "R33") (pin "2") (pinfunction "2_2") (pintype "passive"))
    )
    (net (code "74") (name "Net-(DS4-c)") (class "Default")
      (node (ref "DS4") (pin "4") (pinfunction "c_4") (pintype "passive"))
      (node (ref "R34") (pin "2") (pinfunction "2_2") (pintype "passive"))
    )
    (net (code "75") (name "Net-(DS4-d)") (class "Default")
      (node (ref "DS4") (pin "2") (pinfunction "d_2") (pintype "passive"))
      (node (ref "R35") (pin "2") (pinfunction "2_2") (pintype "passive"))
    )
    (net (code "76") (name "Net-(DS4-e)") (class "Default")
      (node (ref "DS4") (pin "1") (pinfunction "e_1") (pintype "passive"))
      (node (ref "R36") (pin "2") (pinfunction "2_2") (pintype "passive"))
    )
    (net (code "77") (name "Net-(DS4-f)") (class "Default")
      (node (ref "DS4") (pin "9") (pinfunction "f_9") (pintype "passive"))
      (node (ref "R37") (pin "2") (pinfunction "2_2") (pintype "passive"))
    )
    (net (code "78") (name "Net-(DS4-g)") (class "Default")
      (node (ref "DS4") (pin "10") (pinfunction "g_10") (pintype "passive"))
      (node (ref "R38") (pin "2") (pinfunction "2_2") (pintype "passive"))
    )
    (net (code "79") (name "Net-(J4-1)") (class "Default")
      (node (ref "J4") (pin "2") (pinfunction "1_2") (pintype "passive"))
      (node (ref "R7") (pin "2") (pinfunction "2_2") (pintype "passive"))
    )
    (net (code "80") (name "Net-(Q1-B)") (class "Default")
      (node (ref "Q1") (pin "2") (pinfunction "B_2") (pintype "passive"))
      (node (ref "R42") (pin "1") (pinfunction "1_1") (pintype "passive"))
    )
    (net (code "81") (name "Net-(Q1-C)") (class "Default")
      (node (ref "Q1") (pin "3") (pinfunction "C_3") (pintype "passive"))
      (node (ref "R7") (pin "1") (pinfunction "1_1") (pintype "passive"))
    )
    (net (code "82") (name "Net-(U2-QA)") (class "Default")
      (node (ref "R8") (pin "1") (pinfunction "1_1") (pintype "passive"))
      (node (ref "U2") (pin "3") (pinfunction "QA_3") (pintype "output"))
    )
    (net (code "83") (name "Net-(U2-QB)") (class "Default")
      (node (ref "R9") (pin "1") (pinfunction "1_1") (pintype "passive"))
      (node (ref "U2") (pin "4") (pinfunction "QB_4") (pintype "output"))
    )
    (net (code "84") (name "Net-(U2-QC)") (class "Default")
      (node (ref "R10") (pin "1") (pinfunction "1_1") (pintype "passive"))
      (node (ref "U2") (pin "5") (pinfunction "QC_5") (pintype "output"))
    )
    (net (code "85") (name "Net-(U2-QD)") (class "Default")
      (node (ref "R11") (pin "1") (pinfunction "1_1") (pintype "passive"))
      (node (ref "U2") (pin "6") (pinfunction "QD_6") (pintype "output"))
    )
    (net (code "86") (name "Net-(U2-QE)") (class "Default")
      (node (ref "R12") (pin "1") (pinfunction "1_1") (pintype "passive"))
      (node (ref "U2") (pin "10") (pinfunction "QE_10") (pintype "output"))
    )
    (net (code "87") (name "Net-(U2-QF)") (class "Default")
      (node (ref "R13") (pin "1") (pinfunction "1_1") (pintype "passive"))
      (node (ref "U2") (pin "11") (pinfunction "QF_11") (pintype "output"))
    )
    (net (code "88") (name "Net-(U2-QG)") (class "Default")
      (node (ref "R14") (pin "1") (pinfunction "1_1") (pintype "passive"))
      (node (ref "U2") (pin "12") (pinfunction "QG_12") (pintype "output"))
    )
    (net (code "89") (name "Net-(U2-QH)") (class "Default")
      (node (ref "R15") (pin "1") (pinfunction "1_1") (pintype "passive"))
      (node (ref "U2") (pin "13") (pinfunction "QH_13") (pintype "output"))
      (node (ref "U3") (pin "1") (pinfunction "A_1") (pintype "input"))
      (node (ref "U3") (pin "2") (pinfunction "B_2") (pintype "input"))
    )
    (net (code "90") (name "Net-(U3-QA)") (class "Default")
      (node (ref "R16") (pin "1") (pinfunction "1_1") (pintype "passive"))
      (node (ref "U3") (pin "3") (pinfunction "QA_3") (pintype "output"))
    )
    (net (code "91") (name "Net-(U3-QB)") (class "Default")
      (node (ref "R17") (pin "1") (pinfunction "1_1") (pintype "passive"))
      (node (ref "U3") (pin "4") (pinfunction "QB_4") (pintype "output"))
    )
    (net (code "92") (name "Net-(U3-QC)") (class "Default")
      (node (ref "R18") (pin "1") (pinfunction "1_1") (pintype "passive"))
      (node (ref "U3") (pin "5") (pinfunction "QC_5") (pintype "output"))
    )
    (net (code "93") (name "Net-(U3-QD)") (class "Default")
      (node (ref "R19") (pin "1") (pinfunction "1_1") (pintype "passive"))
      (node (ref "U3") (pin "6") (pinfunction "QD_6") (pintype "output"))
    )
    (net (code "94") (name "Net-(U3-QE)") (class "Default")
      (node (ref "R20") (pin "1") (pinfunction "1_1") (pintype "passive"))
      (node (ref "U3") (pin "10") (pinfunction "QE_10") (pintype "output"))
    )
    (net (code "95") (name "Net-(U3-QF)") (class "Default")
      (node (ref "R21") (pin "1") (pinfunction "1_1") (pintype "passive"))
      (node (ref "U3") (pin "11") (pinfunction "QF_11") (pintype "output"))
    )
    (net (code "96") (name "Net-(U3-QG)") (class "Default")
      (node (ref "R22") (pin "1") (pinfunction "1_1") (pintype "passive"))
      (node (ref "U3") (pin "12") (pinfunction "QG_12") (pintype "output"))
    )
    (net (code "97") (name "Net-(U3-QH)") (class "Default")
      (node (ref "R23") (pin "1") (pinfunction "1_1") (pintype "passive"))
      (node (ref "U3") (pin "13") (pinfunction "QH_13") (pintype "output"))
      (node (ref "U4") (pin "1") (pinfunction "A_1") (pintype "input"))
      (node (ref "U4") (pin "2") (pinfunction "B_2") (pintype "input"))
    )
    (net (code "98") (name "Net-(U4-QA)") (class "Default")
      (node (ref "R24") (pin "1") (pinfunction "1_1") (pintype "passive"))
      (node (ref "U4") (pin "3") (pinfunction "QA_3") (pintype "output"))
    )
    (net (code "99") (name "Net-(U4-QB)") (class "Default")
      (node (ref "R25") (pin "1") (pinfunction "1_1") (pintype "passive"))
      (node (ref "U4") (pin "4") (pinfunction "QB_4") (pintype "output"))
    )
    (net (code "100") (name "Net-(U4-QC)") (class "Default")
      (node (ref "R26") (pin "1") (pinfunction "1_1") (pintype "passive"))
      (node (ref "U4") (pin "5") (pinfunction "QC_5") (pintype "output"))
    )
    (net (code "101") (name "Net-(U4-QD)") (class "Default")
      (node (ref "R27") (pin "1") (pinfunction "1_1") (pintype "passive"))
      (node (ref "U4") (pin "6") (pinfunction "QD_6") (pintype "output"))
    )
    (net (code "102") (name "Net-(U4-QE)") (class "Default")
      (node (ref "R28") (pin "1") (pinfunction "1_1") (pintype "passive"))
      (node (ref "U4") (pin "10") (pinfunction "QE_10") (pintype "output"))
    )
    (net (code "103") (name "Net-(U4-QF)") (class "Default")
      (node (ref "R29") (pin "1") (pinfunction "1_1") (pintype "passive"))
      (node (ref "U4") (pin "11") (pinfunction "QF_11") (pintype "output"))
    )
    (net (code "104") (name "Net-(U4-QG)") (class "Default")
      (node (ref "R30") (pin "1") (pinfunction "1_1") (pintype "passive"))
      (node (ref "U4") (pin "12") (pinfunction "QG_12") (pintype "output"))
    )
    (net (code "105") (name "Net-(U4-QH)") (class "Default")
      (node (ref "R31") (pin "1") (pinfunction "1_1") (pintype "passive"))
      (node (ref "U4") (pin "13") (pinfunction "QH_13") (pintype "output"))
      (node (ref "U5") (pin "1") (pinfunction "A_1") (pintype "input"))
      (node (ref "U5") (pin "2") (pinfunction "B_2") (pintype "input"))
    )
    (net (code "106") (name "Net-(U5-QA)") (class "Default")
      (node (ref "R32") (pin "1") (pinfunction "1_1") (pintype "passive"))
      (node (ref "U5") (pin "3") (pinfunction "QA_3") (pintype "output"))
    )
    (net (code "107") (name "Net-(U5-QB)") (class "Default")
      (node (ref "R33") (pin "1") (pinfunction "1_1") (pintype "passive"))
      (node (ref "U5") (pin "4") (pinfunction "QB_4") (pintype "output"))
    )
    (net (code "108") (name "Net-(U5-QC)") (class "Default")
      (node (ref "R34") (pin "1") (pinfunction "1_1") (pintype "passive"))
      (node (ref "U5") (pin "5") (pinfunction "QC_5") (pintype "output"))
    )
    (net (code "109") (name "Net-(U5-QD)") (class "Default")
      (node (ref "R35") (pin "1") (pinfunction "1_1") (pintype "passive"))
      (node (ref "U5") (pin "6") (pinfunction "QD_6") (pintype "output"))
    )
    (net (code "110") (name "Net-(U5-QE)") (class "Default")
      (node (ref "R36") (pin "1") (pinfunction "1_1") (pintype "passive"))
      (node (ref "U5") (pin "10") (pinfunction "QE_10") (pintype "output"))
    )
    (net (code "111") (name "Net-(U5-QF)") (class "Default")
      (node (ref "R37") (pin "1") (pinfunction "1_1") (pintype "passive"))
      (node (ref "U5") (pin "11") (pinfunction "QF_11") (pintype "output"))
    )
    (net (code "112") (name "Net-(U5-QG)") (class "Default")
      (node (ref "R38") (pin "1") (pinfunction "1_1") (pintype "passive"))
      (node (ref "U5") (pin "12") (pinfunction "QG_12") (pintype "output"))
    )
    (net (code "113") (name "Net-(U5-QH)") (class "Default")
      (node (ref "R39") (pin "1") (pinfunction "1_1") (pintype "passive"))
      (node (ref "U5") (pin "13") (pinfunction "QH_13") (pintype "output"))
    )
  )
)
